# design.net
KiCad netlist of a schematic drawn in Altium Designer
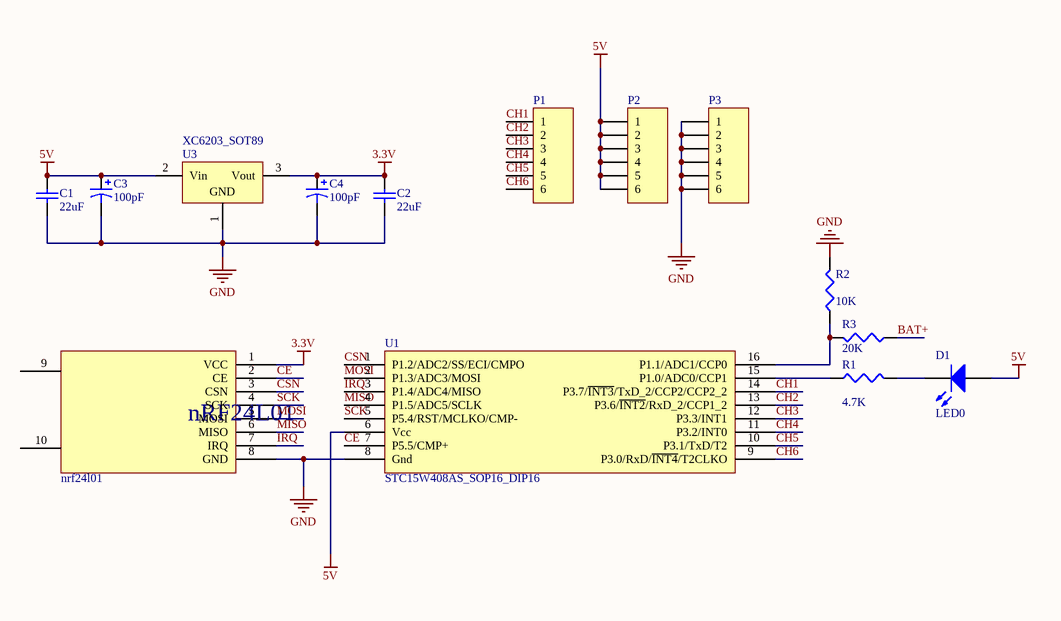
[diagram p0: 原理图.SchDoc]

(export (version "E")
  (design (tool "Eeschema 10.0.6"))
  (components
    (comp (ref "C1")
      (value "22uF")
      (footprint "C 1210_L")
      (description "Capacitor (Semiconductor SIM Model)")
      (fields (field (name "Comment") "Cap Semi") (field (name "PUBLISHER") "Altium Limited"))
      (libsource (lib "Miscellaneous Devices") (part "Cap Semi"))
    )
    (comp (ref "C2")
      (value "22uF")
      (footprint "C 1210_L")
      (description "Capacitor (Semiconductor SIM Model)")
      (fields (field (name "Comment") "Cap Semi") (field (name "PUBLISHER") "Altium Limited"))
      (libsource (lib "Miscellaneous Devices") (part "Cap Semi"))
    )
    (comp (ref "C3")
      (value "100pF")
      (footprint "C 0805_L")
      (description "Polarized Capacitor (Surface Mount)")
      (fields (field (name "Comment") "Cap Pol3") (field (name "PUBLISHER") "Altium Limited"))
      (libsource (lib "Miscellaneous Devices") (part "Cap Pol3"))
    )
    (comp (ref "C4")
      (value "100pF")
      (footprint "C 0805_L")
      (description "Polarized Capacitor (Surface Mount)")
      (fields (field (name "Comment") "Cap Pol3") (field (name "PUBLISHER") "Altium Limited"))
      (libsource (lib "Miscellaneous Devices") (part "Cap Pol3"))
    )
    (comp (ref "D1")
      (value "LED0")
      (footprint "LED 0805B")
      (description "Typical INFRARED GaAs LED")
      (fields (field (name "PUBLISHER") "Altium Limited"))
      (libsource (lib "Miscellaneous Devices") (part "LED0"))
    )
    (comp (ref "P1")
      (value "Header 6")
      (footprint "HDR2.54-LI-6P")
      (description "Header, 6-Pin")
      (fields (field (name "PUBLISHER") "Altium Limited"))
      (libsource (lib "Miscellaneous Connectors") (part "Header 6"))
    )
    (comp (ref "P2")
      (value "Header 6")
      (footprint "HDR2.54-LI-6P")
      (description "Header, 6-Pin")
      (fields (field (name "PUBLISHER") "Altium Limited"))
      (libsource (lib "Miscellaneous Connectors") (part "Header 6"))
    )
    (comp (ref "P3")
      (value "Header 6")
      (footprint "HDR2.54-LI-6P")
      (description "Header, 6-Pin")
      (fields (field (name "PUBLISHER") "Altium Limited"))
      (libsource (lib "Miscellaneous Connectors") (part "Header 6"))
    )
    (comp (ref "R1")
      (value "4.7K")
      (footprint "R 0805_L")
      (description "Resistor")
      (fields (field (name "PUBLISHER") "Altium Limited"))
      (libsource (lib "Miscellaneous Devices") (part "Res3"))
    )
    (comp (ref "R2")
      (value "10K")
      (footprint "R 0805_L")
      (description "Resistor")
      (fields (field (name "Comment") "Res3") (field (name "PUBLISHER") "Altium Limited"))
      (libsource (lib "Miscellaneous Devices") (part "Res3"))
    )
    (comp (ref "R3")
      (value "20K")
      (footprint "R 0805_L")
      (description "Resistor")
      (fields (field (name "Comment") "Res3") (field (name "PUBLISHER") "Altium Limited"))
      (libsource (lib "Miscellaneous Devices") (part "Res3"))
    )
    (comp (ref "U1")
      (value "STC15W408AS_SOP16_DIP16")
      (footprint "SOP16_N")
      (libsource (lib "stcmcu_altium_lib") (part "STC15W401AS_SOP16_DIP16"))
    )
    (comp (ref "U2") (value "nrf24l01") (footprint "nRF24L01") (libsource (lib "原理图库文件") (part "nrf24l01")))
    (comp (ref "U3")
      (value "XC6203_SOT89")
      (footprint "SOT89_N")
      (description "Voltage Regulator")
      (fields (field (name "PUBLISHER") "Altium Limited"))
      (libsource (lib "Miscellaneous Devices") (part "Volt Reg"))
    )
  )
  (nets
    (net (code "1") (name "/BAT+") (class "Default")
      (node (ref "R3") (pin "1") (pinfunction "1_1") (pintype "passive"))
    )
    (net (code "2") (name "/CE") (class "Default")
      (node (ref "U1") (pin "7") (pinfunction "P5.5/CMP+_7") (pintype "passive"))
      (node (ref "U2") (pin "2") (pinfunction "CE_2") (pintype "passive"))
    )
    (net (code "3") (name "/CH1") (class "Default")
      (node (ref "P1") (pin "1") (pinfunction "1_1") (pintype "passive"))
      (node (ref "U1") (pin "14") (pinfunction "P3.7/~{INT3}/TxD_2/CCP2/CCP2_2_14") (pintype "passive"))
    )
    (net (code "4") (name "/CH2") (class "Default")
      (node (ref "P1") (pin "2") (pinfunction "2_2") (pintype "passive"))
      (node (ref "U1") (pin "13") (pinfunction "P3.6/~{INT2}/RxD_2/CCP1_2_13") (pintype "passive"))
    )
    (net (code "5") (name "/CH3") (class "Default")
      (node (ref "P1") (pin "3") (pinfunction "3_3") (pintype "passive"))
      (node (ref "U1") (pin "12") (pinfunction "P3.3/INT1_12") (pintype "passive"))
    )
    (net (code "6") (name "/CH4") (class "Default")
      (node (ref "P1") (pin "4") (pinfunction "4_4") (pintype "passive"))
      (node (ref "U1") (pin "11") (pinfunction "P3.2/INT0_11") (pintype "passive"))
    )
    (net (code "7") (name "/CH5") (class "Default")
      (node (ref "P1") (pin "5") (pinfunction "5_5") (pintype "passive"))
      (node (ref "U1") (pin "10") (pinfunction "P3.1/TxD/T2_10") (pintype "passive"))
    )
    (net (code "8") (name "/CH6") (class "Default")
      (node (ref "P1") (pin "6") (pinfunction "6_6") (pintype "passive"))
      (node (ref "U1") (pin "9") (pinfunction "P3.0/RxD/~{INT4}/T2CLKO_9") (pintype "passive"))
    )
    (net (code "9") (name "/CSN") (class "Default")
      (node (ref "U1") (pin "1") (pinfunction "P1.2/ADC2/SS/ECI/CMPO_1") (pintype "passive"))
      (node (ref "U2") (pin "3") (pinfunction "CSN_3") (pintype "passive"))
    )
    (net (code "10") (name "/IRQ") (class "Default")
      (node (ref "U1") (pin "3") (pinfunction "P1.4/ADC4/MISO_3") (pintype "passive"))
      (node (ref "U2") (pin "7") (pinfunction "IRQ_7") (pintype "passive"))
    )
    (net (code "11") (name "/MISO") (class "Default")
      (node (ref "U1") (pin "4") (pinfunction "P1.5/ADC5/SCLK_4") (pintype "passive"))
      (node (ref "U2") (pin "6") (pinfunction "MISO_6") (pintype "passive"))
    )
    (net (code "12") (name "/MOSI") (class "Default")
      (node (ref "U1") (pin "2") (pinfunction "P1.3/ADC3/MOSI_2") (pintype "passive"))
      (node (ref "U2") (pin "5") (pinfunction "MOSI_5") (pintype "passive"))
    )
    (net (code "13") (name "/SCK") (class "Default")
      (node (ref "U1") (pin "5") (pinfunction "P5.4/RST/MCLKO/CMP-_5") (pintype "passive"))
      (node (ref "U2") (pin "4") (pinfunction "SCK_4") (pintype "passive"))
    )
    (net (code "14") (name "3.3V") (class "Default")
      (node (ref "C2") (pin "2") (pinfunction "2_2") (pintype "passive"))
      (node (ref "C4") (pin "1") (pinfunction "1_1") (pintype "passive"))
      (node (ref "U2") (pin "1") (pinfunction "VCC_1") (pintype "passive"))
      (node (ref "U3") (pin "3") (pinfunction "Vout_3") (pintype "passive"))
    )
    (net (code "15") (name "5V") (class "Default")
      (node (ref "C1") (pin "2") (pinfunction "2_2") (pintype "passive"))
      (node (ref "C3") (pin "1") (pinfunction "1_1") (pintype "passive"))
      (node (ref "D1") (pin "1") (pinfunction "A_1") (pintype "passive"))
      (node (ref "P2") (pin "1") (pinfunction "1_1") (pintype "passive"))
      (node (ref "P2") (pin "2") (pinfunction "2_2") (pintype "passive"))
      (node (ref "P2") (pin "3") (pinfunction "3_3") (pintype "passive"))
      (node (ref "P2") (pin "4") (pinfunction "4_4") (pintype "passive"))
      (node (ref "P2") (pin "5") (pinfunction "5_5") (pintype "passive"))
      (node (ref "P2") (pin "6") (pinfunction "6_6") (pintype "passive"))
      (node (ref "U1") (pin "6") (pinfunction "Vcc_6") (pintype "passive"))
      (node (ref "U3") (pin "2") (pinfunction "Vin_2") (pintype "passive"))
    )
    (net (code "16") (name "GND") (class "Default")
      (node (ref "C1") (pin "1") (pinfunction "1_1") (pintype "passive"))
      (node (ref "C2") (pin "1") (pinfunction "1_1") (pintype "passive"))
      (node (ref "C3") (pin "2") (pinfunction "2_2") (pintype "passive"))
      (node (ref "C4") (pin "2") (pinfunction "2_2") (pintype "passive"))
      (node (ref "P3") (pin "1") (pinfunction "1_1") (pintype "passive"))
      (node (ref "P3") (pin "2") (pinfunction "2_2") (pintype "passive"))
      (node (ref "P3") (pin "3") (pinfunction "3_3") (pintype "passive"))
      (node (ref "P3") (pin "4") (pinfunction "4_4") (pintype "passive"))
      (node (ref "P3") (pin "5") (pinfunction "5_5") (pintype "passive"))
      (node (ref "P3") (pin "6") (pinfunction "6_6") (pintype "passive"))
      (node (ref "R2") (pin "2") (pinfunction "2_2") (pintype "passive"))
      (node (ref "U1") (pin "8") (pinfunction "Gnd_8") (pintype "passive"))
      (node (ref "U2") (pin "8") (pinfunction "GND_8") (pintype "power_in"))
      (node (ref "U3") (pin "1") (pinfunction "GND_1") (pintype "passive"))
    )
    (net (code "17") (name "Net-(D1-K)") (class "Default")
      (node (ref "D1") (pin "2") (pinfunction "K_2") (pintype "passive"))
      (node (ref "R1") (pin "2") (pinfunction "2_2") (pintype "passive"))
    )
    (net (code "18") (name "Net-(U1-P1.0{slash}ADC0{slash}CCP1)") (class "Default")
      (node (ref "R1") (pin "1") (pinfunction "1_1") (pintype "passive"))
      (node (ref "U1") (pin "15") (pinfunction "P1.0/ADC0/CCP1_15") (pintype "passive"))
    )
    (net (code "19") (name "Net-(U1-P1.1{slash}ADC1{slash}CCP0)") (class "Default")
      (node (ref "R2") (pin "1") (pinfunction "1_1") (pintype "passive"))
      (node (ref "R3") (pin "2") (pinfunction "2_2") (pintype "passive"))
      (node (ref "U1") (pin "16") (pinfunction "P1.1/ADC1/CCP0_16") (pintype "passive"))
    )
    (net (code "20") (name "unconnected-(U2-Pad9)") (class "Default")
      (node (ref "U2") (pin "9") (pinfunction "9_9") (pintype "passive"))
    )
    (net (code "21") (name "unconnected-(U2-Pad10)") (class "Default")
      (node (ref "U2") (pin "10") (pinfunction "10_10") (pintype "passive"))
    )
  )
)
